# SENSORS.net
KiCad netlist of a schematic drawn in Altium Designer
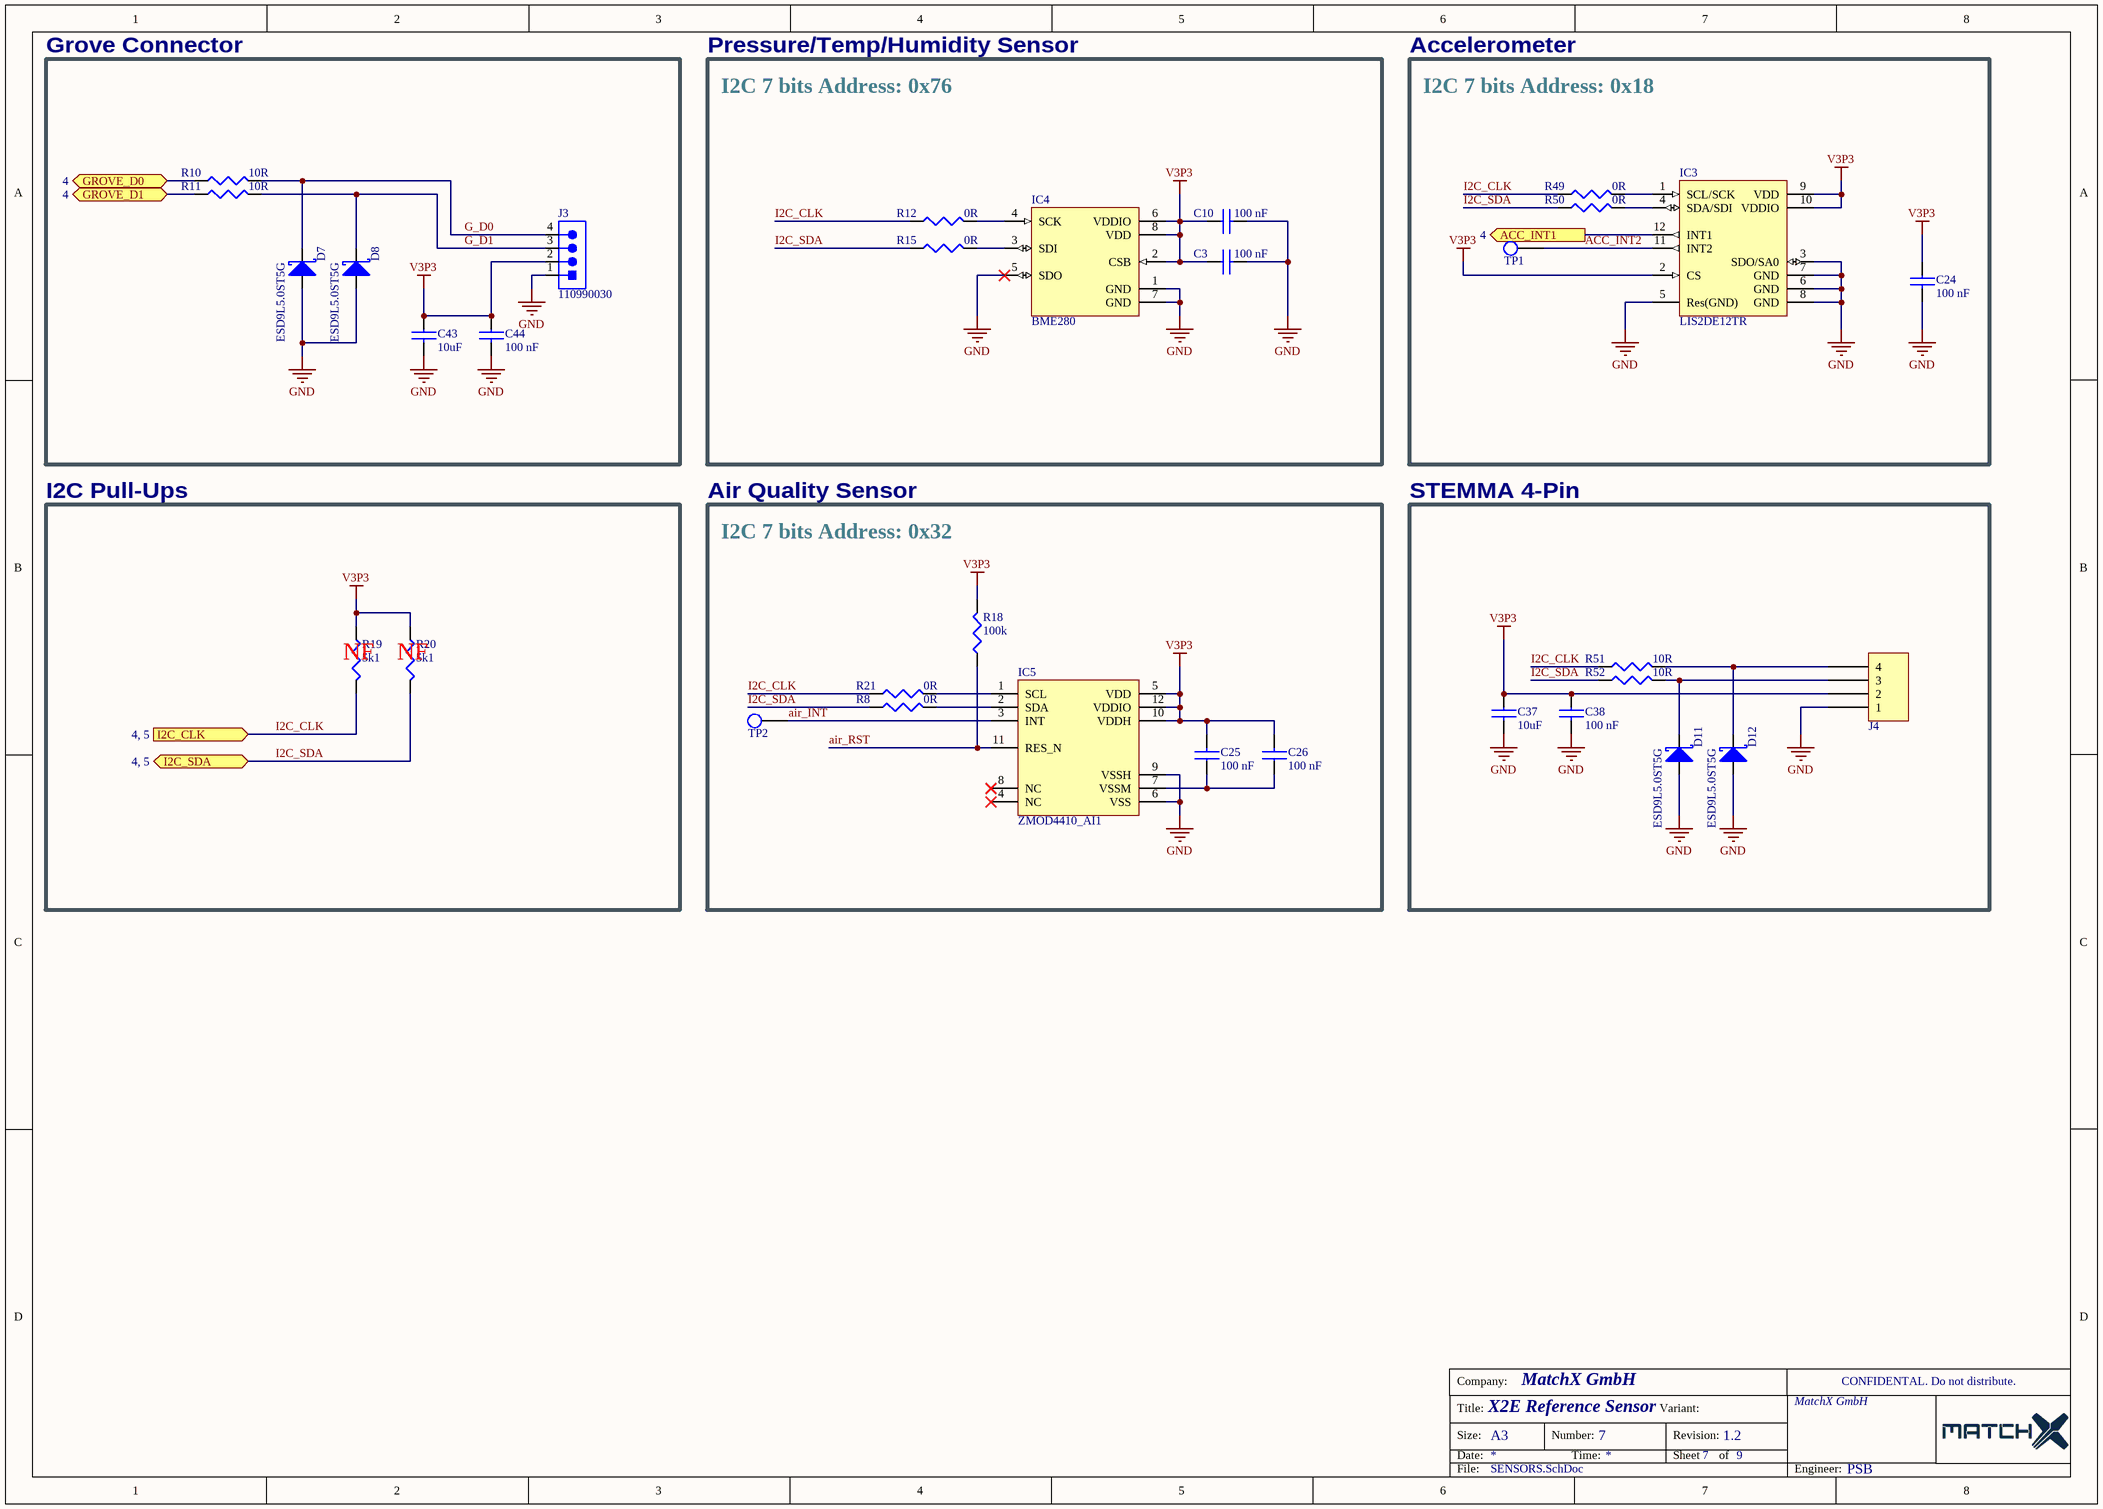
[diagram p0: SENSORS.SchDoc]

(export (version "E")
  (design (tool "Eeschema 10.0.6"))
  (components
    (comp (ref "C3")
      (value "100 nF")
      (footprint "C0402")
      (description "CAP, CERM, 100 nF, 50V, +/- 10%, X7R, 0402")
      (fields (field (name "TOLERANCE") "10%") (field (name "MANUFACTURER PART NUMBER") "GRM155R71H104KE14J"))
      (libsource (lib "psblib") (part "C0402-100nF_50V"))
    )
    (comp (ref "C10")
      (value "100 nF")
      (footprint "C0402")
      (description "CAP, CERM, 100 nF, 50V, +/- 10%, X7R, 0402")
      (fields (field (name "TOLERANCE") "10%") (field (name "MANUFACTURER PART NUMBER") "GRM155R71H104KE14J"))
      (libsource (lib "psblib") (part "C0402-100nF_50V"))
    )
    (comp (ref "C24")
      (value "100 nF")
      (footprint "C0402")
      (description "CAP, CERM, 100 nF, 50V, +/- 10%, X7R, 0402")
      (fields (field (name "TOLERANCE") "10%") (field (name "MANUFACTURER PART NUMBER") "GRM155R71H104KE14J"))
      (libsource (lib "psblib") (part "C0402-100nF_50V"))
    )
    (comp (ref "C25")
      (value "100 nF")
      (footprint "C0402")
      (description "CAP, CERM, 100 nF, 50V, +/- 10%, X7R, 0402")
      (fields (field (name "TOLERANCE") "10%") (field (name "MANUFACTURER PART NUMBER") "GRM155R71H104KE14J"))
      (libsource (lib "psblib") (part "C0402-100nF_50V"))
    )
    (comp (ref "C26")
      (value "100 nF")
      (footprint "C0402")
      (description "CAP, CERM, 100 nF, 50V, +/- 10%, X7R, 0402")
      (fields (field (name "TOLERANCE") "10%") (field (name "MANUFACTURER PART NUMBER") "GRM155R71H104KE14J"))
      (libsource (lib "psblib") (part "C0402-100nF_50V"))
    )
    (comp (ref "C37")
      (value "10uF")
      (footprint "C0805")
      (description "CAP, CERM, 10uF, 16V, +/- 20%, X5R, 0805")
      (fields (field (name "TOLERANCE") "20%") (field (name "MANUFACTURER PART NUMBER") "GRM21BR61C106KE15L"))
      (libsource (lib "psblib") (part "C0805-10uF_16V"))
    )
    (comp (ref "C38")
      (value "100 nF")
      (footprint "C0402")
      (description "CAP, CERM, 100 nF, 50V, +/- 10%, X7R, 0402")
      (fields (field (name "TOLERANCE") "10%") (field (name "MANUFACTURER PART NUMBER") "GRM155R71H104KE14J"))
      (libsource (lib "psblib") (part "C0402-100nF_50V"))
    )
    (comp (ref "C43")
      (value "10uF")
      (footprint "C0805")
      (description "CAP, CERM, 10uF, 16V, +/- 20%, X5R, 0805")
      (fields (field (name "TOLERANCE") "20%") (field (name "MANUFACTURER PART NUMBER") "GRM21BR61C106KE15L"))
      (libsource (lib "psblib") (part "C0805-10uF_16V"))
    )
    (comp (ref "C44")
      (value "100 nF")
      (footprint "C0402")
      (description "CAP, CERM, 100 nF, 50V, +/- 10%, X7R, 0402")
      (fields (field (name "TOLERANCE") "10%") (field (name "MANUFACTURER PART NUMBER") "GRM155R71H104KE14J"))
      (libsource (lib "psblib") (part "C0402-100nF_50V"))
    )
    (comp (ref "D7")
      (value "ESD9L5.0ST5G")
      (footprint "SOD-923")
      (description "TVS DIODE 5V 9.8V SOD923")
      (fields (field (name "MANUFACTURER") "ON Semiconductor"))
      (libsource (lib "psblib") (part "TVSUni_ESD9L5.0ST5G"))
    )
    (comp (ref "D8")
      (value "ESD9L5.0ST5G")
      (footprint "SOD-923")
      (description "TVS DIODE 5V 9.8V SOD923")
      (fields (field (name "MANUFACTURER") "ON Semiconductor"))
      (libsource (lib "psblib") (part "TVSUni_ESD9L5.0ST5G"))
    )
    (comp (ref "D11")
      (value "ESD9L5.0ST5G")
      (footprint "SOD-923")
      (description "TVS DIODE 5V 9.8V SOD923")
      (fields (field (name "MANUFACTURER") "ON Semiconductor"))
      (libsource (lib "psblib") (part "TVSUni_ESD9L5.0ST5G"))
    )
    (comp (ref "D12")
      (value "ESD9L5.0ST5G")
      (footprint "SOD-923")
      (description "TVS DIODE 5V 9.8V SOD923")
      (fields (field (name "MANUFACTURER") "ON Semiconductor"))
      (libsource (lib "psblib") (part "TVSUni_ESD9L5.0ST5G"))
    )
    (comp (ref "IC3")
      (value "LIS2DE12TR")
      (footprint "LGA12C50P4X4_200X200X100")
      (description "Accelerometer X, Y, Z Axis ±2g, 4g, 8g, 16g 0.5Hz ~ 2.69kHz 12-LGA (2x2)")
      (fields
        (field (name "MANUFACTURER") "STMicroelectronics")
        (field (name ".CHECKED PCB") "OK M")
        (field (name ".CHECKED SCH") "OK M")
      )
      (libsource (lib "psblib") (part "ST=LIS2DE12"))
    )
    (comp (ref "IC4")
      (value "BME280")
      (footprint "LGA65P250X250-8")
      (description "SENSOR PRESSURE HUMIDITY TEMP")
      (fields (field (name "MANUFACTURER") "Bosch"))
      (libsource (lib "psblib") (part "BOSH=BME280"))
    )
    (comp (ref "IC5")
      (value "ZMOD4410_AI1")
      (footprint "ZMOD4xxx_AI1_Standard")
      (description "Indoor Air Quality Sensor")
      (fields (field (name "MANUFACTURER") "Renesas"))
      (libsource (lib "psblib") (part "Renesas=ZMOD4410_AI1"))
    )
    (comp (ref "J3")
      (value "110990030")
      (footprint "CON-NS-TECH_1125S-4P")
      (description "4 Positions Header Connector 0.079\" (2.00mm) Through Hole Tin")
      (fields (field (name "MANUFACTURER") "Seeed Studio"))
      (libsource (lib "psblib") (part "CON_SeedStudio_110990030"))
    )
    (comp (ref "J4")
      (value "~")
      (footprint "JST S4B-PH-SM4-TB")
      (description "CONN HEADER SMD R/A 4POS 2MM")
      (fields
        (field (name "MANUFACTURER PART NUMBER") "1734827-4")
        (field (name "MANUFACTURER") "JST Sales America Inc.")
      )
      (libsource (lib "psblib") (part "CON-JST S4B-PH-SM4-TB"))
    )
    (comp (ref "R8")
      (value "0R")
      (footprint "R0402")
      (description "RES, 0R, 1%, 1/16 W, 0402")
      (fields
        (field (name "TOLERANCE") "±1%")
        (field (name "MANUFACTURER PART NUMBER") "AC0402FR-070RL")
        (field (name ".CHECKED PCB") "OK RF")
        (field (name ".CHECKED SCH") "RF")
      )
      (libsource (lib "psblib") (part "R0402-0R"))
    )
    (comp (ref "R10")
      (value "10R")
      (footprint "R0402")
      (description "RES, 10R, 1%, 1/16 W, 0402")
      (fields
        (field (name "TOLERANCE") "±1%")
        (field (name "MANUFACTURER PART NUMBER") "RC0402FR-0710RP")
        (field (name ".CHECKED PCB") "OK RF")
        (field (name ".CHECKED SCH") "RF")
      )
      (libsource (lib "psblib") (part "R0402-10R"))
    )
    (comp (ref "R11")
      (value "10R")
      (footprint "R0402")
      (description "RES, 10R, 1%, 1/16 W, 0402")
      (fields
        (field (name "TOLERANCE") "±1%")
        (field (name "MANUFACTURER PART NUMBER") "RC0402FR-0710RP")
        (field (name ".CHECKED PCB") "OK RF")
        (field (name ".CHECKED SCH") "RF")
      )
      (libsource (lib "psblib") (part "R0402-10R"))
    )
    (comp (ref "R12")
      (value "0R")
      (footprint "R0402")
      (description "RES, 0R, 1%, 1/16 W, 0402")
      (fields
        (field (name "TOLERANCE") "±1%")
        (field (name "MANUFACTURER PART NUMBER") "AC0402FR-070RL")
        (field (name ".CHECKED PCB") "OK RF")
        (field (name ".CHECKED SCH") "RF")
      )
      (libsource (lib "psblib") (part "R0402-0R"))
    )
    (comp (ref "R15")
      (value "0R")
      (footprint "R0402")
      (description "RES, 0R, 1%, 1/16 W, 0402")
      (fields
        (field (name "TOLERANCE") "±1%")
        (field (name "MANUFACTURER PART NUMBER") "AC0402FR-070RL")
        (field (name ".CHECKED PCB") "OK RF")
        (field (name ".CHECKED SCH") "RF")
      )
      (libsource (lib "psblib") (part "R0402-0R"))
    )
    (comp (ref "R18")
      (value "100k")
      (footprint "R0402")
      (description "RES, 100k, 1%, 1/16 W, 0402")
      (fields
        (field (name "TOLERANCE") "±1%")
        (field (name "MANUFACTURER PART NUMBER") "AC0402FR-13100KL")
        (field (name ".CHECKED PCB") "OK RF")
        (field (name ".CHECKED SCH") "RF")
      )
      (libsource (lib "psblib") (part "R0402-100k"))
    )
    (comp (ref "R19")
      (value "5k1")
      (footprint "R0603")
      (description "RES, 5k1, 1%, 0.063 W, 0603")
      (fields
        (field (name "TOLERANCE") "±1%")
        (field (name "MANUFACTURER PART NUMBER") "AC0603FR-135K1L")
        (field (name ".CHECKED PCB") "OK RF")
        (field (name ".CHECKED SCH") "RF")
      )
      (libsource (lib "psblib") (part "R0603-5k1"))
    )
    (comp (ref "R20")
      (value "5k1")
      (footprint "R0603")
      (description "RES, 5k1, 1%, 0.063 W, 0603")
      (fields
        (field (name "TOLERANCE") "±1%")
        (field (name "MANUFACTURER PART NUMBER") "AC0603FR-135K1L")
        (field (name ".CHECKED PCB") "OK RF")
        (field (name ".CHECKED SCH") "RF")
      )
      (libsource (lib "psblib") (part "R0603-5k1"))
    )
    (comp (ref "R21")
      (value "0R")
      (footprint "R0402")
      (description "RES, 0R, 1%, 1/16 W, 0402")
      (fields
        (field (name "TOLERANCE") "±1%")
        (field (name "MANUFACTURER PART NUMBER") "AC0402FR-070RL")
        (field (name ".CHECKED PCB") "OK RF")
        (field (name ".CHECKED SCH") "RF")
      )
      (libsource (lib "psblib") (part "R0402-0R"))
    )
    (comp (ref "R49")
      (value "0R")
      (footprint "R0402")
      (description "RES, 0R, 1%, 1/16 W, 0402")
      (fields
        (field (name "TOLERANCE") "±1%")
        (field (name "MANUFACTURER PART NUMBER") "AC0402FR-070RL")
        (field (name ".CHECKED PCB") "OK RF")
        (field (name ".CHECKED SCH") "RF")
      )
      (libsource (lib "psblib") (part "R0402-0R"))
    )
    (comp (ref "R50")
      (value "0R")
      (footprint "R0402")
      (description "RES, 0R, 1%, 1/16 W, 0402")
      (fields
        (field (name "TOLERANCE") "±1%")
        (field (name "MANUFACTURER PART NUMBER") "AC0402FR-070RL")
        (field (name ".CHECKED PCB") "OK RF")
        (field (name ".CHECKED SCH") "RF")
      )
      (libsource (lib "psblib") (part "R0402-0R"))
    )
    (comp (ref "R51")
      (value "10R")
      (footprint "R0402")
      (description "RES, 10R, 1%, 1/16 W, 0402")
      (fields
        (field (name "TOLERANCE") "±1%")
        (field (name "MANUFACTURER PART NUMBER") "RC0402FR-0710RP")
        (field (name ".CHECKED PCB") "OK RF")
        (field (name ".CHECKED SCH") "RF")
      )
      (libsource (lib "psblib") (part "R0402-10R"))
    )
    (comp (ref "R52")
      (value "10R")
      (footprint "R0402")
      (description "RES, 10R, 1%, 1/16 W, 0402")
      (fields
        (field (name "TOLERANCE") "±1%")
        (field (name "MANUFACTURER PART NUMBER") "RC0402FR-0710RP")
        (field (name ".CHECKED PCB") "OK RF")
        (field (name ".CHECKED SCH") "RF")
      )
      (libsource (lib "psblib") (part "R0402-10R"))
    )
    (comp (ref "TP1")
      (value "TP")
      (footprint "TP_SMD_1.5mm")
      (description "Test Point")
      (libsource (lib "psblib") (part "TP"))
    )
    (comp (ref "TP2")
      (value "TP")
      (footprint "TP_SMD_1.5mm")
      (description "Test Point")
      (libsource (lib "psblib") (part "TP"))
    )
  )
  (nets
    (net (code "1") (name "/ACC_INT1") (class "Default")
      (node (ref "IC3") (pin "12") (pinfunction "INT1_12") (pintype "output"))
    )
    (net (code "2") (name "/ACC_INT2") (class "Default")
      (node (ref "IC3") (pin "11") (pinfunction "INT2_11") (pintype "output"))
      (node (ref "TP1") (pin "0") (pinfunction "0_0") (pintype "passive"))
    )
    (net (code "3") (name "/GROVE_D0") (class "Default")
      (node (ref "R10") (pin "2") (pinfunction "2_2") (pintype "passive"))
    )
    (net (code "4") (name "/GROVE_D1") (class "Default")
      (node (ref "R11") (pin "2") (pinfunction "2_2") (pintype "passive"))
    )
    (net (code "5") (name "/G_D0") (class "Default")
      (node (ref "D7") (pin "1") (pinfunction "A_1") (pintype "passive"))
      (node (ref "J3") (pin "4") (pinfunction "4_4") (pintype "passive"))
      (node (ref "R10") (pin "1") (pinfunction "1_1") (pintype "passive"))
    )
    (net (code "6") (name "/G_D1") (class "Default")
      (node (ref "D8") (pin "1") (pinfunction "A_1") (pintype "passive"))
      (node (ref "J3") (pin "3") (pinfunction "3_3") (pintype "passive"))
      (node (ref "R11") (pin "1") (pinfunction "1_1") (pintype "passive"))
    )
    (net (code "7") (name "/I2C_CLK") (class "Default")
      (node (ref "R12") (pin "1") (pinfunction "1_1") (pintype "passive"))
      (node (ref "R19") (pin "1") (pinfunction "1_1") (pintype "passive"))
      (node (ref "R21") (pin "1") (pinfunction "1_1") (pintype "passive"))
      (node (ref "R49") (pin "1") (pinfunction "1_1") (pintype "passive"))
      (node (ref "R51") (pin "2") (pinfunction "2_2") (pintype "passive"))
    )
    (net (code "8") (name "/I2C_SDA") (class "Default")
      (node (ref "R15") (pin "1") (pinfunction "1_1") (pintype "passive"))
      (node (ref "R20") (pin "1") (pinfunction "1_1") (pintype "passive"))
      (node (ref "R50") (pin "1") (pinfunction "1_1") (pintype "passive"))
      (node (ref "R52") (pin "2") (pinfunction "2_2") (pintype "passive"))
      (node (ref "R8") (pin "1") (pinfunction "1_1") (pintype "passive"))
    )
    (net (code "9") (name "/air_INT") (class "Default")
      (node (ref "IC5") (pin "3") (pinfunction "INT_3") (pintype "passive"))
      (node (ref "TP2") (pin "0") (pinfunction "0_0") (pintype "passive"))
    )
    (net (code "10") (name "/air_RST") (class "Default")
      (node (ref "IC5") (pin "11") (pinfunction "RES_N_11") (pintype "passive"))
      (node (ref "R18") (pin "1") (pinfunction "1_1") (pintype "passive"))
    )
    (net (code "11") (name "GND") (class "Default")
      (node (ref "C10") (pin "2") (pinfunction "2_2") (pintype "passive"))
      (node (ref "C24") (pin "2") (pinfunction "2_2") (pintype "passive"))
      (node (ref "C3") (pin "2") (pinfunction "2_2") (pintype "passive"))
      (node (ref "C37") (pin "2") (pinfunction "2_2") (pintype "passive"))
      (node (ref "C38") (pin "2") (pinfunction "2_2") (pintype "passive"))
      (node (ref "C43") (pin "2") (pinfunction "2_2") (pintype "passive"))
      (node (ref "C44") (pin "2") (pinfunction "2_2") (pintype "passive"))
      (node (ref "D11") (pin "2") (pinfunction "K_2") (pintype "passive"))
      (node (ref "D12") (pin "2") (pinfunction "K_2") (pintype "passive"))
      (node (ref "D7") (pin "2") (pinfunction "K_2") (pintype "passive"))
      (node (ref "D8") (pin "2") (pinfunction "K_2") (pintype "passive"))
      (node (ref "IC3") (pin "3") (pinfunction "SDO/SA0_3") (pintype "bidirectional"))
      (node (ref "IC3") (pin "5") (pinfunction "Res(GND)_5") (pintype "passive"))
      (node (ref "IC3") (pin "6") (pinfunction "GND_6") (pintype "passive"))
      (node (ref "IC3") (pin "7") (pinfunction "GND_7") (pintype "passive"))
      (node (ref "IC3") (pin "8") (pinfunction "GND_8") (pintype "passive"))
      (node (ref "IC4") (pin "1") (pinfunction "GND_1") (pintype "passive"))
      (node (ref "IC4") (pin "5") (pinfunction "SDO_5") (pintype "bidirectional"))
      (node (ref "IC4") (pin "7") (pinfunction "GND_7") (pintype "passive"))
      (node (ref "IC5") (pin "6") (pinfunction "VSS_6") (pintype "passive"))
      (node (ref "IC5") (pin "9") (pinfunction "VSSH_9") (pintype "passive"))
      (node (ref "J3") (pin "1") (pinfunction "1_1") (pintype "passive"))
      (node (ref "J4") (pin "1") (pinfunction "1_1") (pintype "passive"))
    )
    (net (code "12") (name "Net-(D11-A)") (class "Default")
      (node (ref "D11") (pin "1") (pinfunction "A_1") (pintype "passive"))
      (node (ref "J4") (pin "3") (pinfunction "3_3") (pintype "passive"))
      (node (ref "R52") (pin "1") (pinfunction "1_1") (pintype "passive"))
    )
    (net (code "13") (name "Net-(D12-A)") (class "Default")
      (node (ref "D12") (pin "1") (pinfunction "A_1") (pintype "passive"))
      (node (ref "J4") (pin "4") (pinfunction "4_4") (pintype "passive"))
      (node (ref "R51") (pin "1") (pinfunction "1_1") (pintype "passive"))
    )
    (net (code "14") (name "Net-(IC3-SCL{slash}SCK)") (class "Default")
      (node (ref "IC3") (pin "1") (pinfunction "SCL/SCK_1") (pintype "input"))
      (node (ref "R49") (pin "2") (pinfunction "2_2") (pintype "passive"))
    )
    (net (code "15") (name "Net-(IC3-SDA{slash}SDI)") (class "Default")
      (node (ref "IC3") (pin "4") (pinfunction "SDA/SDI_4") (pintype "bidirectional"))
      (node (ref "R50") (pin "2") (pinfunction "2_2") (pintype "passive"))
    )
    (net (code "16") (name "Net-(IC4-SCK)") (class "Default")
      (node (ref "IC4") (pin "4") (pinfunction "SCK_4") (pintype "input"))
      (node (ref "R12") (pin "2") (pinfunction "2_2") (pintype "passive"))
    )
    (net (code "17") (name "Net-(IC4-SDI)") (class "Default")
      (node (ref "IC4") (pin "3") (pinfunction "SDI_3") (pintype "bidirectional"))
      (node (ref "R15") (pin "2") (pinfunction "2_2") (pintype "passive"))
    )
    (net (code "18") (name "Net-(IC5-SCL)") (class "Default")
      (node (ref "IC5") (pin "1") (pinfunction "SCL_1") (pintype "passive"))
      (node (ref "R21") (pin "2") (pinfunction "2_2") (pintype "passive"))
    )
    (net (code "19") (name "Net-(IC5-SDA)") (class "Default")
      (node (ref "IC5") (pin "2") (pinfunction "SDA_2") (pintype "passive"))
      (node (ref "R8") (pin "2") (pinfunction "2_2") (pintype "passive"))
    )
    (net (code "20") (name "Net-(IC5-VSSM)") (class "Default")
      (node (ref "C25") (pin "1") (pinfunction "1_1") (pintype "passive"))
      (node (ref "C26") (pin "1") (pinfunction "1_1") (pintype "passive"))
      (node (ref "IC5") (pin "7") (pinfunction "VSSM_7") (pintype "passive"))
    )
    (net (code "21") (name "V3P3") (class "Default")
      (node (ref "C10") (pin "1") (pinfunction "1_1") (pintype "passive"))
      (node (ref "C24") (pin "1") (pinfunction "1_1") (pintype "passive"))
      (node (ref "C25") (pin "2") (pinfunction "2_2") (pintype "passive"))
      (node (ref "C26") (pin "2") (pinfunction "2_2") (pintype "passive"))
      (node (ref "C3") (pin "1") (pinfunction "1_1") (pintype "passive"))
      (node (ref "C37") (pin "1") (pinfunction "1_1") (pintype "passive"))
      (node (ref "C38") (pin "1") (pinfunction "1_1") (pintype "passive"))
      (node (ref "C43") (pin "1") (pinfunction "1_1") (pintype "passive"))
      (node (ref "C44") (pin "1") (pinfunction "1_1") (pintype "passive"))
      (node (ref "IC3") (pin "10") (pinfunction "VDDIO_10") (pintype "power_in"))
      (node (ref "IC3") (pin "2") (pinfunction "CS_2") (pintype "input"))
      (node (ref "IC3") (pin "9") (pinfunction "VDD_9") (pintype "power_in"))
      (node (ref "IC4") (pin "2") (pinfunction "CSB_2") (pintype "input"))
      (node (ref "IC4") (pin "6") (pinfunction "VDDIO_6") (pintype "power_in"))
      (node (ref "IC4") (pin "8") (pinfunction "VDD_8") (pintype "power_in"))
      (node (ref "IC5") (pin "10") (pinfunction "VDDH_10") (pintype "passive"))
      (node (ref "IC5") (pin "12") (pinfunction "VDDIO_12") (pintype "passive"))
      (node (ref "IC5") (pin "5") (pinfunction "VDD_5") (pintype "passive"))
      (node (ref "J3") (pin "2") (pinfunction "2_2") (pintype "passive"))
      (node (ref "J4") (pin "2") (pinfunction "2_2") (pintype "passive"))
      (node (ref "R18") (pin "2") (pinfunction "2_2") (pintype "passive"))
      (node (ref "R19") (pin "2") (pinfunction "2_2") (pintype "passive"))
      (node (ref "R20") (pin "2") (pinfunction "2_2") (pintype "passive"))
    )
    (net (code "22") (name "unconnected-(IC5-NC-Pad4)") (class "Default")
      (node (ref "IC5") (pin "4") (pinfunction "NC_4") (pintype "passive+no_connect"))
    )
    (net (code "23") (name "unconnected-(IC5-NC-Pad8)") (class "Default")
      (node (ref "IC5") (pin "8") (pinfunction "NC_8") (pintype "passive+no_connect"))
    )
  )
)
